# PCB_Schematic_Layout.net
KiCad netlist of a schematic drawn in EasyEDA
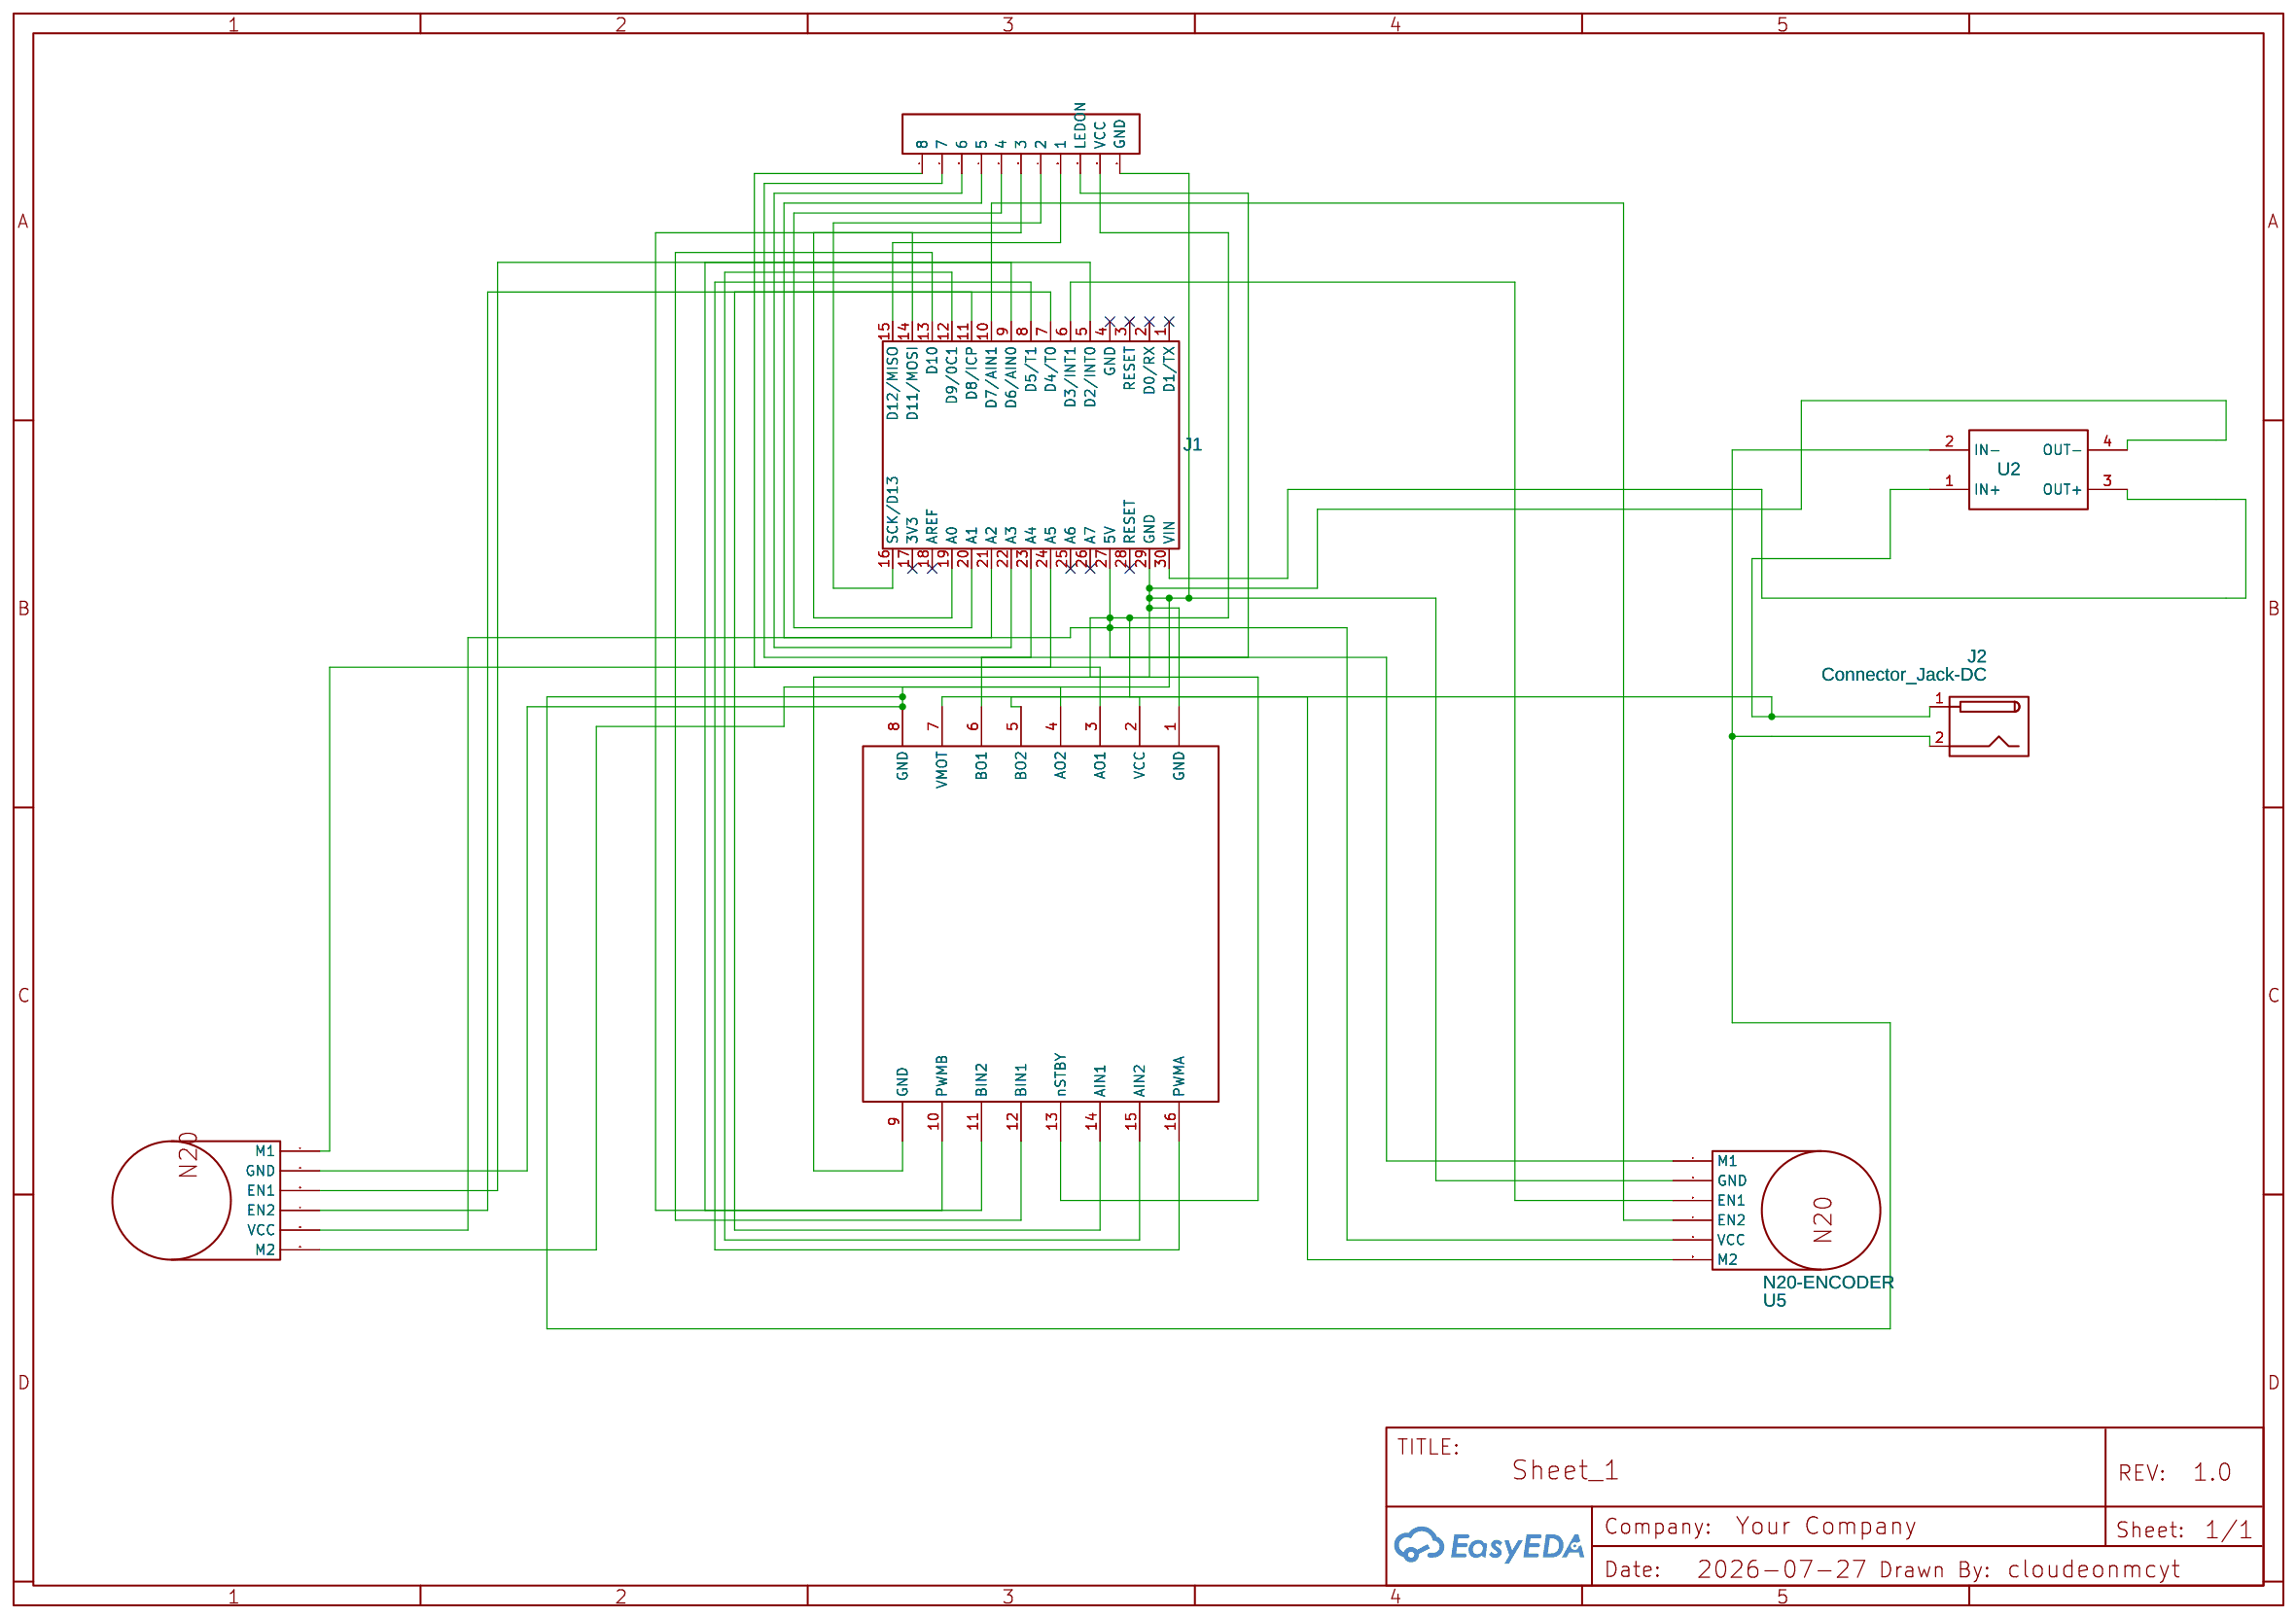
[diagram p0: schematic sheet]

(export (version "E")
  (design (tool "Eeschema 10.0.6"))
  (components
    (comp (ref "J1") (value "Arduino_Nano_Header") (libsource (lib "") (part "Arduino_Nano_Header")))
    (comp (ref "J2") (value "Connector_Jack-DC") (libsource (lib "") (part "Connector_Jack-DC")))
    (comp (ref "P1") (value "Header-Female-2.54_1x11") (libsource (lib "") (part "Header-Female-2.54_1x11")))
    (comp (ref "U1")
      (value "TB6612FNG Dual Motor Driver Carrier")
      (libsource (lib "") (part "TB6612FNG Dual Motor Driver Carrier"))
    )
    (comp (ref "U2") (value "MP1584EN") (libsource (lib "") (part "MP1584EN")))
    (comp (ref "U5") (value "N20-ENCODER") (libsource (lib "") (part "N20-ENCODER_1")))
    (comp (ref "U6") (value "N20-ENCODER") (libsource (lib "") (part "N20-ENCODER")))
  )
  (nets
    (net (code "1") (name "Net-(J1-5V)") (class "Default")
      (node (ref "J1") (pin "27") (pinfunction "5V_27") (pintype "unspecified"))
      (node (ref "P1") (pin "10") (pinfunction "VCC_10") (pintype "input"))
      (node (ref "P1") (pin "9") (pinfunction "LEDON_9") (pintype "input"))
      (node (ref "U1") (pin "13") (pinfunction "nSTBY_13") (pintype "unspecified"))
      (node (ref "U1") (pin "2") (pinfunction "VCC_2") (pintype "unspecified"))
      (node (ref "U5") (pin "5") (pinfunction "VCC_5") (pintype "unspecified"))
      (node (ref "U6") (pin "5") (pinfunction "VCC_5") (pintype "unspecified"))
    )
    (net (code "2") (name "Net-(J1-A0)") (class "Default")
      (node (ref "J1") (pin "19") (pinfunction "A0_19") (pintype "unspecified"))
      (node (ref "P1") (pin "6") (pinfunction "3_6") (pintype "input"))
    )
    (net (code "3") (name "Net-(J1-A1)") (class "Default")
      (node (ref "J1") (pin "20") (pinfunction "A1_20") (pintype "unspecified"))
      (node (ref "P1") (pin "5") (pinfunction "4_5") (pintype "input"))
    )
    (net (code "4") (name "Net-(J1-A2)") (class "Default")
      (node (ref "J1") (pin "21") (pinfunction "A2_21") (pintype "unspecified"))
      (node (ref "P1") (pin "4") (pinfunction "5_4") (pintype "input"))
    )
    (net (code "5") (name "Net-(J1-A3)") (class "Default")
      (node (ref "J1") (pin "22") (pinfunction "A3_22") (pintype "unspecified"))
      (node (ref "P1") (pin "3") (pinfunction "6_3") (pintype "input"))
    )
    (net (code "6") (name "Net-(J1-A4)") (class "Default")
      (node (ref "J1") (pin "23") (pinfunction "A4_23") (pintype "unspecified"))
      (node (ref "P1") (pin "2") (pinfunction "7_2") (pintype "input"))
    )
    (net (code "7") (name "Net-(J1-A5)") (class "Default")
      (node (ref "J1") (pin "24") (pinfunction "A5_24") (pintype "unspecified"))
      (node (ref "P1") (pin "1") (pinfunction "8_1") (pintype "input"))
    )
    (net (code "8") (name "Net-(J1-D2{slash}INT0)") (class "Default")
      (node (ref "J1") (pin "5") (pinfunction "D2/INT0_5") (pintype "unspecified"))
      (node (ref "U6") (pin "3") (pinfunction "EN1_3") (pintype "unspecified"))
    )
    (net (code "9") (name "Net-(J1-D3{slash}INT1)") (class "Default")
      (node (ref "J1") (pin "6") (pinfunction "D3/INT1_6") (pintype "unspecified"))
      (node (ref "U5") (pin "3") (pinfunction "EN1_3") (pintype "unspecified"))
    )
    (net (code "10") (name "Net-(J1-D4{slash}T0)") (class "Default")
      (node (ref "J1") (pin "7") (pinfunction "D4/T0_7") (pintype "unspecified"))
      (node (ref "U6") (pin "4") (pinfunction "EN2_4") (pintype "unspecified"))
    )
    (net (code "11") (name "Net-(J1-D5{slash}T1)") (class "Default")
      (node (ref "J1") (pin "8") (pinfunction "D5/T1_8") (pintype "unspecified"))
      (node (ref "U1") (pin "16") (pinfunction "PWMA_16") (pintype "unspecified"))
    )
    (net (code "12") (name "Net-(J1-D6{slash}AIN0)") (class "Default")
      (node (ref "J1") (pin "9") (pinfunction "D6/AIN0_9") (pintype "unspecified"))
      (node (ref "U1") (pin "10") (pinfunction "PWMB_10") (pintype "unspecified"))
    )
    (net (code "13") (name "Net-(J1-D7{slash}AIN1)") (class "Default")
      (node (ref "J1") (pin "10") (pinfunction "D7/AIN1_10") (pintype "unspecified"))
      (node (ref "U5") (pin "4") (pinfunction "EN2_4") (pintype "unspecified"))
    )
    (net (code "14") (name "Net-(J1-D8{slash}ICP)") (class "Default")
      (node (ref "J1") (pin "11") (pinfunction "D8/ICP_11") (pintype "unspecified"))
      (node (ref "U1") (pin "14") (pinfunction "AIN1_14") (pintype "unspecified"))
    )
    (net (code "15") (name "Net-(J1-D9{slash}0C1)") (class "Default")
      (node (ref "J1") (pin "12") (pinfunction "D9/0C1_12") (pintype "unspecified"))
      (node (ref "U1") (pin "15") (pinfunction "AIN2_15") (pintype "unspecified"))
    )
    (net (code "16") (name "Net-(J1-D10)") (class "Default")
      (node (ref "J1") (pin "13") (pinfunction "D10_13") (pintype "unspecified"))
      (node (ref "U1") (pin "12") (pinfunction "BIN1_12") (pintype "unspecified"))
    )
    (net (code "17") (name "Net-(J1-D11{slash}MOSI)") (class "Default")
      (node (ref "J1") (pin "14") (pinfunction "D11/MOSI_14") (pintype "unspecified"))
      (node (ref "U1") (pin "11") (pinfunction "BIN2_11") (pintype "unspecified"))
    )
    (net (code "18") (name "Net-(J1-D12{slash}MISO)") (class "Default")
      (node (ref "J1") (pin "15") (pinfunction "D12/MISO_15") (pintype "unspecified"))
      (node (ref "P1") (pin "8") (pinfunction "1_8") (pintype "input"))
    )
    (net (code "19") (name "Net-(J1-SCK{slash}D13)") (class "Default")
      (node (ref "J1") (pin "16") (pinfunction "SCK/D13_16") (pintype "unspecified"))
      (node (ref "P1") (pin "7") (pinfunction "2_7") (pintype "input"))
    )
    (net (code "20") (name "Net-(J1-VIN)") (class "Default")
      (node (ref "J1") (pin "30") (pinfunction "VIN_30") (pintype "unspecified"))
      (node (ref "U2") (pin "3") (pinfunction "OUT+_3") (pintype "unspecified"))
    )
    (net (code "21") (name "Net-(P1-GND)") (class "Default")
      (node (ref "J1") (pin "29") (pinfunction "GND_29") (pintype "unspecified"))
      (node (ref "J2") (pin "2") (pintype "unspecified"))
      (node (ref "P1") (pin "11") (pinfunction "GND_11") (pintype "input"))
      (node (ref "U1") (pin "1") (pinfunction "GND_1") (pintype "unspecified"))
      (node (ref "U1") (pin "8") (pinfunction "GND_8") (pintype "unspecified"))
      (node (ref "U1") (pin "9") (pinfunction "GND_9") (pintype "unspecified"))
      (node (ref "U2") (pin "2") (pinfunction "IN-_2") (pintype "unspecified"))
      (node (ref "U2") (pin "4") (pinfunction "OUT-_4") (pintype "unspecified"))
      (node (ref "U5") (pin "2") (pinfunction "GND_2") (pintype "unspecified"))
      (node (ref "U6") (pin "2") (pinfunction "GND_2") (pintype "unspecified"))
    )
    (net (code "22") (name "Net-(U1-AO1)") (class "Default")
      (node (ref "U1") (pin "3") (pinfunction "AO1_3") (pintype "unspecified"))
      (node (ref "U6") (pin "1") (pinfunction "M1_1") (pintype "unspecified"))
    )
    (net (code "23") (name "Net-(U1-AO2)") (class "Default")
      (node (ref "U1") (pin "4") (pinfunction "AO2_4") (pintype "unspecified"))
      (node (ref "U6") (pin "6") (pinfunction "M2_6") (pintype "unspecified"))
    )
    (net (code "24") (name "Net-(U1-BO1)") (class "Default")
      (node (ref "U1") (pin "6") (pinfunction "BO1_6") (pintype "unspecified"))
      (node (ref "U5") (pin "1") (pinfunction "M1_1") (pintype "unspecified"))
    )
    (net (code "25") (name "Net-(U1-BO2)") (class "Default")
      (node (ref "U1") (pin "5") (pinfunction "BO2_5") (pintype "unspecified"))
      (node (ref "U5") (pin "6") (pinfunction "M2_6") (pintype "unspecified"))
    )
    (net (code "26") (name "Net-(U1-VMOT)") (class "Default")
      (node (ref "J2") (pin "1") (pintype "unspecified"))
      (node (ref "U1") (pin "7") (pinfunction "VMOT_7") (pintype "unspecified"))
      (node (ref "U2") (pin "1") (pinfunction "IN+_1") (pintype "unspecified"))
    )
    (net (code "27") (name "unconnected-(J1-3V3-Pad17)") (class "Default")
      (node (ref "J1") (pin "17") (pinfunction "3V3_17") (pintype "unspecified+no_connect"))
    )
    (net (code "28") (name "unconnected-(J1-A6-Pad25)") (class "Default")
      (node (ref "J1") (pin "25") (pinfunction "A6_25") (pintype "unspecified+no_connect"))
    )
    (net (code "29") (name "unconnected-(J1-A7-Pad26)") (class "Default")
      (node (ref "J1") (pin "26") (pinfunction "A7_26") (pintype "unspecified+no_connect"))
    )
    (net (code "30") (name "unconnected-(J1-AREF-Pad18)") (class "Default")
      (node (ref "J1") (pin "18") (pinfunction "AREF_18") (pintype "unspecified+no_connect"))
    )
    (net (code "31") (name "unconnected-(J1-D0{slash}RX-Pad2)") (class "Default")
      (node (ref "J1") (pin "2") (pinfunction "D0/RX_2") (pintype "unspecified+no_connect"))
    )
    (net (code "32") (name "unconnected-(J1-D1{slash}TX-Pad1)") (class "Default")
      (node (ref "J1") (pin "1") (pinfunction "D1/TX_1") (pintype "unspecified+no_connect"))
    )
    (net (code "33") (name "unconnected-(J1-GND-Pad4)") (class "Default")
      (node (ref "J1") (pin "4") (pinfunction "GND_4") (pintype "unspecified+no_connect"))
    )
    (net (code "34") (name "unconnected-(J1-RESET-Pad3)") (class "Default")
      (node (ref "J1") (pin "3") (pinfunction "RESET_3") (pintype "unspecified+no_connect"))
    )
    (net (code "35") (name "unconnected-(J1-RESET-Pad28)") (class "Default")
      (node (ref "J1") (pin "28") (pinfunction "RESET_28") (pintype "unspecified+no_connect"))
    )
  )
)
